# IMU_6DoF.net
KiCad netlist of a schematic drawn in EAGLE
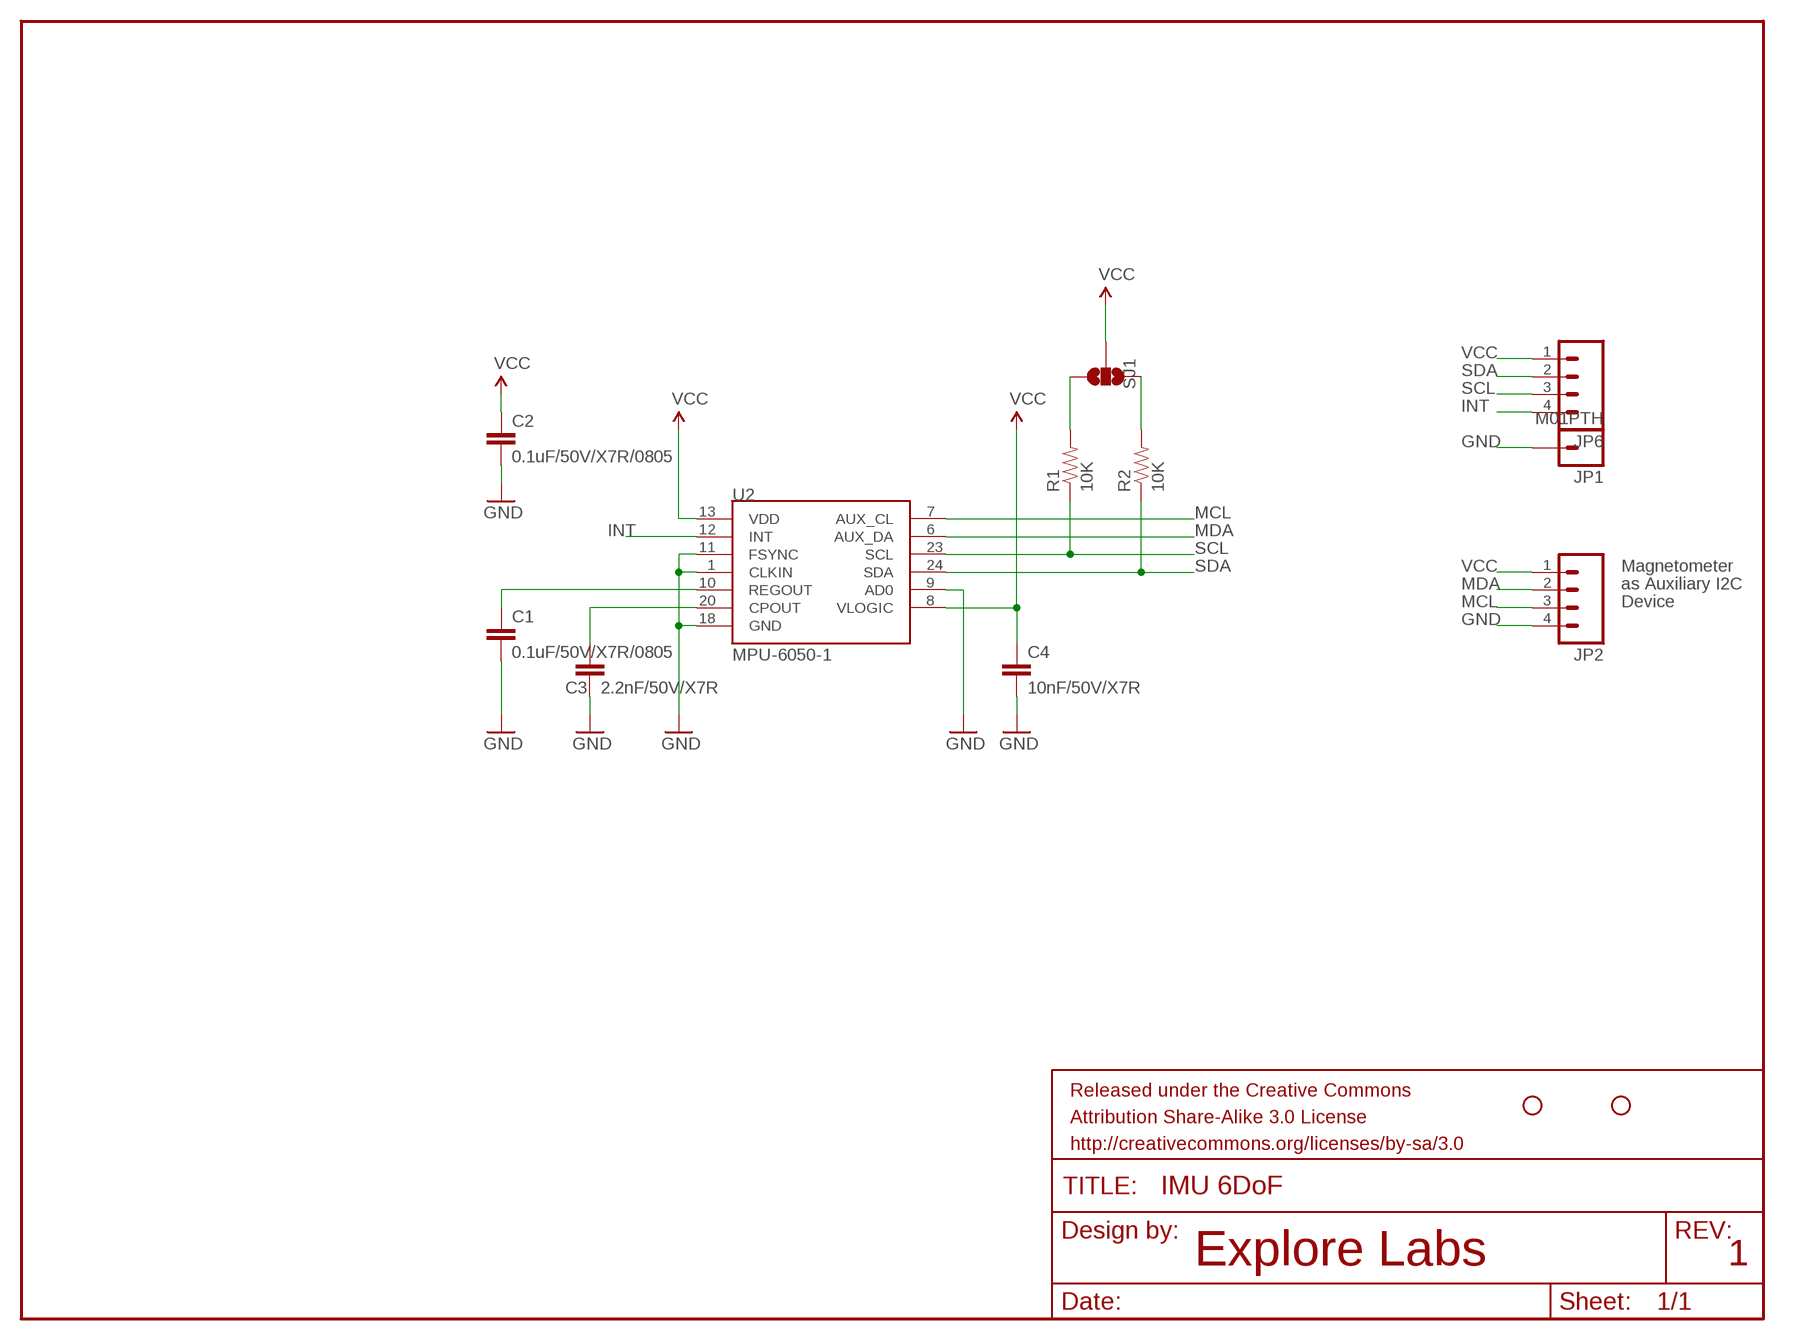
[diagram p0: schematic, sheet 1]

(export (version "E")
  (design (tool "Eeschema 10.0.6"))
  (components
    (comp (ref "C1")
      (value "0.1uF/50V/X7R/0805")
      (footprint "eagle-import:0805")
      (libsource (lib "eagle-import") (part "CAP0805"))
    )
    (comp (ref "C2")
      (value "0.1uF/50V/X7R/0805")
      (footprint "eagle-import:0805")
      (libsource (lib "eagle-import") (part "CAP0805"))
    )
    (comp (ref "C3")
      (value "2.2nF/50V/X7R")
      (footprint "eagle-import:0805")
      (libsource (lib "eagle-import") (part "CAP0805"))
    )
    (comp (ref "C4")
      (value "10nF/50V/X7R")
      (footprint "eagle-import:0805")
      (libsource (lib "eagle-import") (part "CAP0805"))
    )
    (comp (ref "JP1")
      (value "M01PTH")
      (footprint "eagle-import:1X01")
      (libsource (lib "eagle-import") (part "M01PTH"))
    )
    (comp (ref "JP2")
      (value "M04PTH")
      (footprint "eagle-import:1X04")
      (libsource (lib "eagle-import") (part "M04PTH"))
    )
    (comp (ref "JP3")
      (value "STAND-OFFTIGHT")
      (footprint "eagle-import:STAND-OFF-TIGHT")
      (libsource (lib "eagle-import") (part "STAND-OFFTIGHT"))
    )
    (comp (ref "JP4")
      (value "STAND-OFFTIGHT")
      (footprint "eagle-import:STAND-OFF-TIGHT")
      (libsource (lib "eagle-import") (part "STAND-OFFTIGHT"))
    )
    (comp (ref "JP6")
      (value "M04PTH")
      (footprint "eagle-import:1X04")
      (libsource (lib "eagle-import") (part "M04PTH"))
    )
    (comp (ref "R1")
      (value "10K")
      (footprint "eagle-import:0603-RES")
      (libsource (lib "eagle-import") (part "RESISTOR0603-RES"))
    )
    (comp (ref "R2")
      (value "10K")
      (footprint "eagle-import:0603-RES")
      (libsource (lib "eagle-import") (part "RESISTOR0603-RES"))
    )
    (comp (ref "SJ1")
      (value "SOLDERJUMPER_2WAYT")
      (footprint "eagle-import:SJ_2")
      (libsource (lib "eagle-import") (part "SOLDERJUMPER_2WAYT"))
    )
    (comp (ref "U2")
      (value "MPU-6050-1")
      (footprint "eagle-import:QFN-24-4MM2")
      (libsource (lib "eagle-import") (part "MPU-6050-1"))
    )
  )
  (nets
    (net (code "1") (name "/INT") (class "Default")
      (node (ref "JP6") (pin "4") (pinfunction "4_4") (pintype "passive"))
      (node (ref "U2") (pin "12") (pinfunction "INT_12") (pintype "bidirectional"))
    )
    (net (code "2") (name "/MCL") (class "Default")
      (node (ref "JP2") (pin "3") (pinfunction "3_3") (pintype "passive"))
      (node (ref "U2") (pin "7") (pinfunction "AUX_CL_7") (pintype "bidirectional"))
    )
    (net (code "3") (name "/MDA") (class "Default")
      (node (ref "JP2") (pin "2") (pinfunction "2_2") (pintype "passive"))
      (node (ref "U2") (pin "6") (pinfunction "AUX_DA_6") (pintype "bidirectional"))
    )
    (net (code "4") (name "/SCL") (class "Default")
      (node (ref "JP6") (pin "3") (pinfunction "3_3") (pintype "passive"))
      (node (ref "R1") (pin "1") (pinfunction "1_1") (pintype "passive"))
      (node (ref "U2") (pin "23") (pinfunction "SCL_23") (pintype "bidirectional"))
    )
    (net (code "5") (name "/SDA") (class "Default")
      (node (ref "JP6") (pin "2") (pinfunction "2_2") (pintype "passive"))
      (node (ref "R2") (pin "1") (pinfunction "1_1") (pintype "passive"))
      (node (ref "U2") (pin "24") (pinfunction "SDA_24") (pintype "bidirectional"))
    )
    (net (code "6") (name "GND") (class "Default")
      (node (ref "C1") (pin "2") (pinfunction "2_2") (pintype "passive"))
      (node (ref "C2") (pin "2") (pinfunction "2_2") (pintype "passive"))
      (node (ref "C3") (pin "2") (pinfunction "2_2") (pintype "passive"))
      (node (ref "C4") (pin "2") (pinfunction "2_2") (pintype "passive"))
      (node (ref "JP1") (pin "1") (pinfunction "1_1") (pintype "passive"))
      (node (ref "JP2") (pin "4") (pinfunction "4_4") (pintype "passive"))
      (node (ref "U2") (pin "1") (pinfunction "CLKIN_1") (pintype "bidirectional"))
      (node (ref "U2") (pin "11") (pinfunction "FSYNC_11") (pintype "bidirectional"))
      (node (ref "U2") (pin "18") (pinfunction "GND_18") (pintype "bidirectional"))
      (node (ref "U2") (pin "9") (pinfunction "AD0_9") (pintype "bidirectional"))
    )
    (net (code "7") (name "Net-(R1-Pad2)") (class "Default")
      (node (ref "R1") (pin "2") (pinfunction "2_2") (pintype "passive"))
      (node (ref "SJ1") (pin "3") (pinfunction "3_3") (pintype "passive"))
    )
    (net (code "8") (name "Net-(R2-Pad2)") (class "Default")
      (node (ref "R2") (pin "2") (pinfunction "2_2") (pintype "passive"))
      (node (ref "SJ1") (pin "1") (pinfunction "1_1") (pintype "passive"))
    )
    (net (code "9") (name "Net-(U2-CPOUT)") (class "Default")
      (node (ref "C3") (pin "1") (pinfunction "1_1") (pintype "passive"))
      (node (ref "U2") (pin "20") (pinfunction "CPOUT_20") (pintype "bidirectional"))
    )
    (net (code "10") (name "Net-(U2-REGOUT)") (class "Default")
      (node (ref "C1") (pin "1") (pinfunction "1_1") (pintype "passive"))
      (node (ref "U2") (pin "10") (pinfunction "REGOUT_10") (pintype "bidirectional"))
    )
    (net (code "11") (name "VCC") (class "Default")
      (node (ref "C2") (pin "1") (pinfunction "1_1") (pintype "passive"))
      (node (ref "C4") (pin "1") (pinfunction "1_1") (pintype "passive"))
      (node (ref "JP2") (pin "1") (pinfunction "1_1") (pintype "passive"))
      (node (ref "JP6") (pin "1") (pinfunction "1_1") (pintype "passive"))
      (node (ref "SJ1") (pin "2") (pinfunction "2_2") (pintype "passive"))
      (node (ref "U2") (pin "13") (pinfunction "VDD_13") (pintype "bidirectional"))
      (node (ref "U2") (pin "8") (pinfunction "VLOGIC_8") (pintype "bidirectional"))
    )
  )
)
